# GAGAN_container_V1.net
KiCad netlist of a schematic drawn in EAGLE
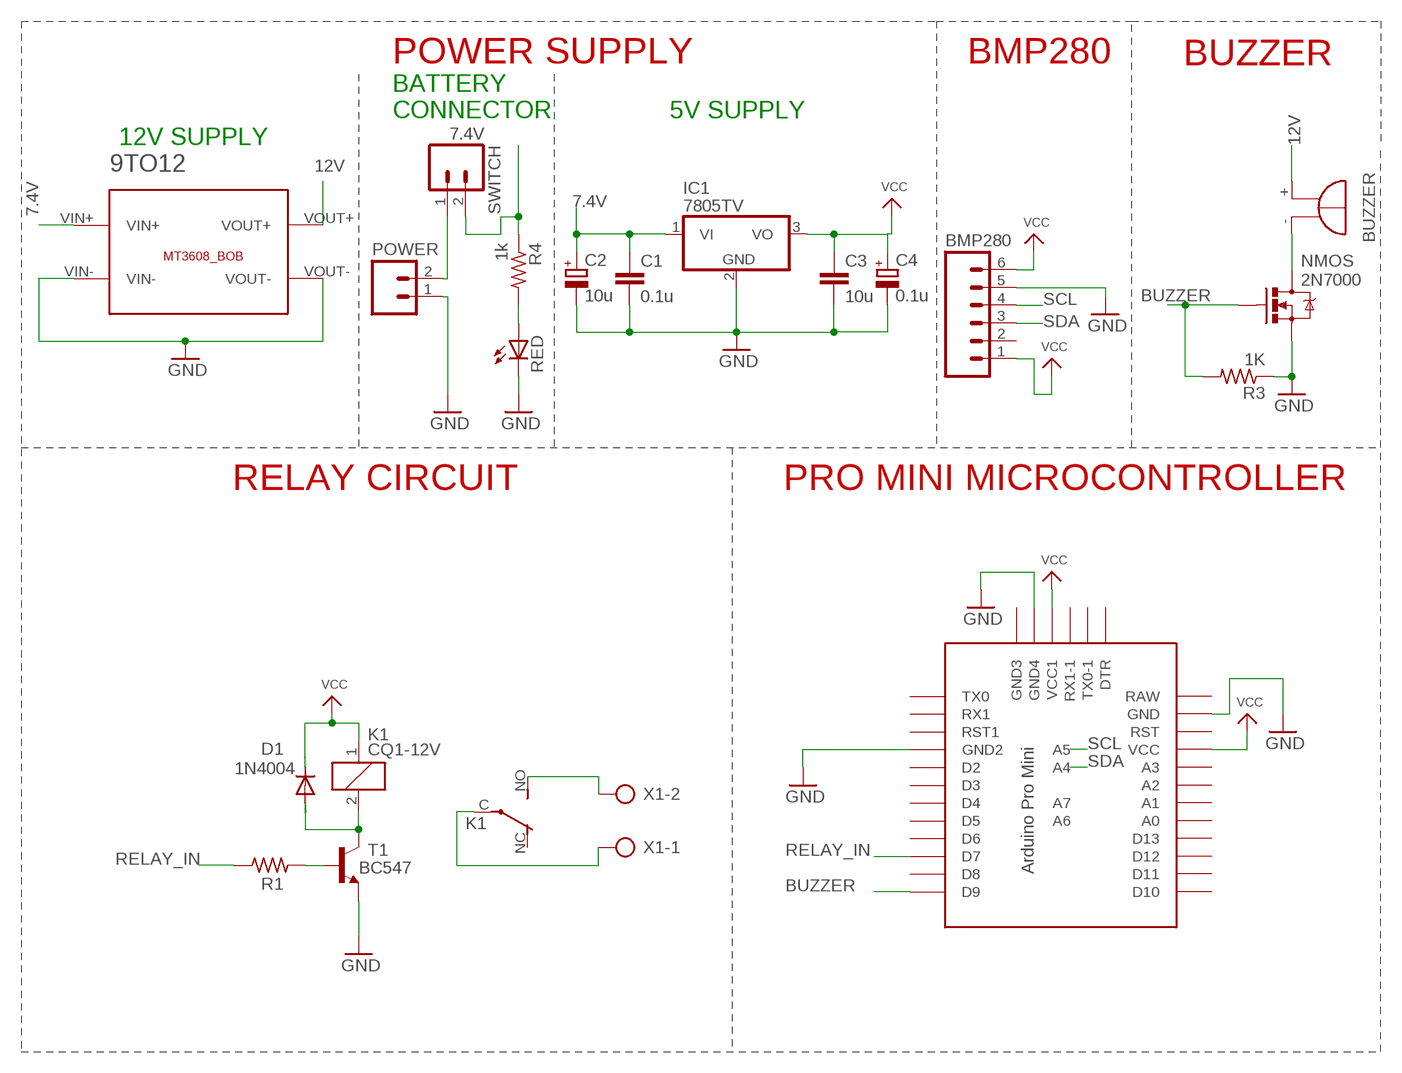
[diagram p0: schematic, sheet 1]

(export (version "E")
  (design (tool "Eeschema 10.0.6"))
  (components
    (comp (ref "9TO12")
      (value "BREAKOUTS_MT3608_BOB")
      (footprint "eagle-import:BREAKOUTS_MT3608_BOB")
      (libsource (lib "eagle-import") (part "BREAKOUTS_MT3608_BOB"))
    )
    (comp (ref "BMP280")
      (value "M06")
      (footprint "eagle-import:06P")
      (libsource (lib "eagle-import") (part "M06"))
    )
    (comp (ref "C1")
      (value "0.1u")
      (footprint "eagle-import:C025-025X050")
      (libsource (lib "eagle-import") (part "C-EU025-025X050"))
    )
    (comp (ref "C2")
      (value "10u")
      (footprint "eagle-import:E2,5-6")
      (libsource (lib "eagle-import") (part "CPOL-EUE2.5-6"))
    )
    (comp (ref "C3")
      (value "10u")
      (footprint "eagle-import:C025-025X050")
      (libsource (lib "eagle-import") (part "C-EU025-025X050"))
    )
    (comp (ref "C4")
      (value "0.1u")
      (footprint "eagle-import:E2,5-6")
      (libsource (lib "eagle-import") (part "CPOL-EUE2.5-6"))
    )
    (comp (ref "D1")
      (value "1N4004")
      (footprint "eagle-import:DO41-10")
      (libsource (lib "eagle-import") (part "1N4004"))
    )
    (comp (ref "IC1")
      (value "7805TV")
      (footprint "eagle-import:TO220V")
      (libsource (lib "eagle-import") (part "78TV05"))
    )
    (comp (ref "K1")
      (value "CQ1-12V")
      (footprint "eagle-import:CQ1")
      (libsource (lib "eagle-import") (part "CQ1-12V"))
    )
    (comp (ref "POWER")
      (value "CEDT_JANUARY_2015_V5_M02")
      (footprint "eagle-import:CEDT_JANUARY_2015_V5_02P")
      (libsource (lib "eagle-import") (part "CEDT_JANUARY_2015_V5_M02"))
    )
    (comp (ref "Q1")
      (value "SPARKFUN-DISCRETESEMI_MOSFET-NCHANNEL2N7000")
      (footprint "eagle-import:SPARKFUN-DISCRETESEMI_TO-92")
      (libsource (lib "eagle-import") (part "SPARKFUN-DISCRETESEMI_MOSFET-NCHANNEL2N7000"))
    )
    (comp (ref "R1")
      (value "R-US_0207/7")
      (footprint "eagle-import:0207_7")
      (libsource (lib "eagle-import") (part "R-US_0207/7"))
    )
    (comp (ref "R3")
      (value "1K")
      (footprint "eagle-import:0204_7")
      (libsource (lib "eagle-import") (part "R-US_0204/7"))
    )
    (comp (ref "R4")
      (value "1k")
      (footprint "eagle-import:0204_7")
      (libsource (lib "eagle-import") (part "R-US_0204/7"))
    )
    (comp (ref "RED")
      (value "red")
      (footprint "eagle-import:LED3MM")
      (libsource (lib "eagle-import") (part "LED3MM"))
    )
    (comp (ref "SG1")
      (value "BUZZER_EB2209A")
      (footprint "eagle-import:BUZZER_EB2209A")
      (libsource (lib "eagle-import") (part "BUZZER_EB2209A"))
    )
    (comp (ref "SWITCH")
      (value "M02")
      (footprint "eagle-import:02P")
      (libsource (lib "eagle-import") (part "M02"))
    )
    (comp (ref "T1")
      (value "BC547")
      (footprint "eagle-import:TO92")
      (libsource (lib "eagle-import") (part "BC547"))
    )
    (comp (ref "U$1")
      (value "PRO-MINI-2")
      (footprint "eagle-import:PRO-MINI-2")
      (libsource (lib "eagle-import") (part "PRO-MINI-2"))
    )
    (comp (ref "X1")
      (value "AK500/2-H")
      (footprint "eagle-import:AK500_2-H")
      (libsource (lib "eagle-import") (part "AK500/2-H"))
    )
  )
  (nets
    (net (code "1") (name "/7.4V") (class "Default")
      (node (ref "9TO12") (pin "VIN+") (pinfunction "VIN+_VIN+") (pintype "bidirectional"))
      (node (ref "C1") (pin "1") (pinfunction "1_1") (pintype "passive"))
      (node (ref "C2") (pin "+") (pinfunction "+_+") (pintype "passive"))
      (node (ref "IC1") (pin "1") (pinfunction "VI_1") (pintype "input"))
      (node (ref "R4") (pin "1") (pinfunction "1_1") (pintype "passive"))
      (node (ref "SWITCH") (pin "2") (pinfunction "2_2") (pintype "passive"))
    )
    (net (code "2") (name "/12V") (class "Default")
      (node (ref "9TO12") (pin "VOUT+") (pinfunction "VOUT+_VOUT+") (pintype "bidirectional"))
      (node (ref "SG1") (pin "+") (pinfunction "+_+") (pintype "passive"))
    )
    (net (code "3") (name "/BUZZER") (class "Default")
      (node (ref "Q1") (pin "2") (pinfunction "G_2") (pintype "passive"))
      (node (ref "R3") (pin "2") (pinfunction "2_2") (pintype "passive"))
      (node (ref "U$1") (pin "D9") (pinfunction "D9_D9") (pintype "bidirectional"))
    )
    (net (code "4") (name "/RELAY_IN") (class "Default")
      (node (ref "R1") (pin "1") (pinfunction "1_1") (pintype "passive"))
      (node (ref "U$1") (pin "D7") (pinfunction "D7_D7") (pintype "bidirectional"))
    )
    (net (code "5") (name "/SCL") (class "Default")
      (node (ref "BMP280") (pin "4") (pinfunction "4_4") (pintype "passive"))
      (node (ref "U$1") (pin "A5") (pinfunction "A5_A5") (pintype "bidirectional"))
    )
    (net (code "6") (name "/SDA") (class "Default")
      (node (ref "BMP280") (pin "3") (pinfunction "3_3") (pintype "passive"))
      (node (ref "U$1") (pin "A4") (pinfunction "A4_A4") (pintype "bidirectional"))
    )
    (net (code "7") (name "GND") (class "Default")
      (node (ref "9TO12") (pin "VIN-") (pinfunction "VIN-_VIN-") (pintype "bidirectional"))
      (node (ref "9TO12") (pin "VOUT-") (pinfunction "VOUT-_VOUT-") (pintype "bidirectional"))
      (node (ref "BMP280") (pin "5") (pinfunction "5_5") (pintype "passive"))
      (node (ref "C1") (pin "2") (pinfunction "2_2") (pintype "passive"))
      (node (ref "C2") (pin "-") (pinfunction "-_-") (pintype "passive"))
      (node (ref "C3") (pin "2") (pinfunction "2_2") (pintype "passive"))
      (node (ref "C4") (pin "-") (pinfunction "-_-") (pintype "passive"))
      (node (ref "IC1") (pin "2") (pinfunction "GND_2") (pintype "passive"))
      (node (ref "POWER") (pin "1") (pinfunction "1_1") (pintype "passive"))
      (node (ref "Q1") (pin "1") (pinfunction "S_1") (pintype "passive"))
      (node (ref "R3") (pin "1") (pinfunction "1_1") (pintype "passive"))
      (node (ref "RED") (pin "K") (pinfunction "C_K") (pintype "passive"))
      (node (ref "T1") (pin "1") (pinfunction "E_1") (pintype "passive"))
      (node (ref "U$1") (pin "GND") (pinfunction "GND_GND") (pintype "bidirectional"))
      (node (ref "U$1") (pin "GND1") (pinfunction "GND2_GND1") (pintype "bidirectional"))
      (node (ref "U$1") (pin "GND3") (pinfunction "GND4_GND3") (pintype "bidirectional"))
    )
    (net (code "8") (name "Net-(K1B-P)") (class "Default")
      (node (ref "K1") (pin "C") (pinfunction "P_C") (pintype "passive"))
      (node (ref "X1") (pin "1") (pinfunction "KL_1") (pintype "passive"))
    )
    (net (code "9") (name "Net-(K1B-S)") (class "Default")
      (node (ref "K1") (pin "NO") (pinfunction "S_NO") (pintype "passive"))
      (node (ref "X1") (pin "2") (pinfunction "KL_2") (pintype "passive"))
    )
    (net (code "10") (name "Net-(POWER-Pad2)") (class "Default")
      (node (ref "POWER") (pin "2") (pinfunction "2_2") (pintype "passive"))
      (node (ref "SWITCH") (pin "1") (pinfunction "1_1") (pintype "passive"))
    )
    (net (code "11") (name "Net-(Q1-D)") (class "Default")
      (node (ref "Q1") (pin "3") (pinfunction "D_3") (pintype "passive"))
      (node (ref "SG1") (pin "-") (pinfunction "-_-") (pintype "passive"))
    )
    (net (code "12") (name "Net-(R4-Pad2)") (class "Default")
      (node (ref "R4") (pin "2") (pinfunction "2_2") (pintype "passive"))
      (node (ref "RED") (pin "A") (pinfunction "A_A") (pintype "passive"))
    )
    (net (code "13") (name "Net-(T1-B)") (class "Default")
      (node (ref "R1") (pin "2") (pinfunction "2_2") (pintype "passive"))
      (node (ref "T1") (pin "2") (pinfunction "B_2") (pintype "passive"))
    )
    (net (code "14") (name "Net-(T1-C)") (class "Default")
      (node (ref "D1") (pin "A") (pinfunction "A_A") (pintype "passive"))
      (node (ref "K1") (pin "2") (pinfunction "2_2") (pintype "passive"))
      (node (ref "T1") (pin "3") (pinfunction "C_3") (pintype "passive"))
    )
    (net (code "15") (name "VCC") (class "Default")
      (node (ref "BMP280") (pin "1") (pinfunction "1_1") (pintype "passive"))
      (node (ref "BMP280") (pin "6") (pinfunction "6_6") (pintype "passive"))
      (node (ref "C3") (pin "1") (pinfunction "1_1") (pintype "passive"))
      (node (ref "C4") (pin "+") (pinfunction "+_+") (pintype "passive"))
      (node (ref "D1") (pin "C") (pinfunction "C_C") (pintype "passive"))
      (node (ref "IC1") (pin "3") (pinfunction "VO_3") (pintype "passive"))
      (node (ref "K1") (pin "1") (pinfunction "1_1") (pintype "passive"))
      (node (ref "U$1") (pin "VCC") (pinfunction "VCC_VCC") (pintype "bidirectional"))
      (node (ref "U$1") (pin "VCC1") (pinfunction "VCC1_VCC1") (pintype "bidirectional"))
    )
    (net (code "16") (name "unconnected-(BMP280-Pad2)") (class "Default")
      (node (ref "BMP280") (pin "2") (pinfunction "2_2") (pintype "passive"))
    )
    (net (code "17") (name "unconnected-(K1B-O-PadNC)") (class "Default")
      (node (ref "K1") (pin "NC") (pinfunction "O_NC") (pintype "passive"))
    )
    (net (code "18") (name "unconnected-(U$1-GND3-PadGND2)") (class "Default")
      (node (ref "U$1") (pin "GND2") (pinfunction "GND3_GND2") (pintype "bidirectional"))
    )
    (net (code "19") (name "unconnected-(U$1-PadA0)") (class "Default")
      (node (ref "U$1") (pin "A0") (pinfunction "A0_A0") (pintype "bidirectional"))
    )
    (net (code "20") (name "unconnected-(U$1-PadA1)") (class "Default")
      (node (ref "U$1") (pin "A1") (pinfunction "A1_A1") (pintype "bidirectional"))
    )
    (net (code "21") (name "unconnected-(U$1-PadA2)") (class "Default")
      (node (ref "U$1") (pin "A2") (pinfunction "A2_A2") (pintype "bidirectional"))
    )
    (net (code "22") (name "unconnected-(U$1-PadA3)") (class "Default")
      (node (ref "U$1") (pin "A3") (pinfunction "A3_A3") (pintype "bidirectional"))
    )
    (net (code "23") (name "unconnected-(U$1-PadA6)") (class "Default")
      (node (ref "U$1") (pin "A6") (pinfunction "A6_A6") (pintype "bidirectional"))
    )
    (net (code "24") (name "unconnected-(U$1-PadA7)") (class "Default")
      (node (ref "U$1") (pin "A7") (pinfunction "A7_A7") (pintype "bidirectional"))
    )
    (net (code "25") (name "unconnected-(U$1-PadD2)") (class "Default")
      (node (ref "U$1") (pin "D2") (pinfunction "D2_D2") (pintype "bidirectional"))
    )
    (net (code "26") (name "unconnected-(U$1-PadD3)") (class "Default")
      (node (ref "U$1") (pin "D3") (pinfunction "D3_D3") (pintype "bidirectional"))
    )
    (net (code "27") (name "unconnected-(U$1-PadD4)") (class "Default")
      (node (ref "U$1") (pin "D4") (pinfunction "D4_D4") (pintype "bidirectional"))
    )
    (net (code "28") (name "unconnected-(U$1-PadD5)") (class "Default")
      (node (ref "U$1") (pin "D5") (pinfunction "D5_D5") (pintype "bidirectional"))
    )
    (net (code "29") (name "unconnected-(U$1-PadD6)") (class "Default")
      (node (ref "U$1") (pin "D6") (pinfunction "D6_D6") (pintype "bidirectional"))
    )
    (net (code "30") (name "unconnected-(U$1-PadD8)") (class "Default")
      (node (ref "U$1") (pin "D8") (pinfunction "D8_D8") (pintype "bidirectional"))
    )
    (net (code "31") (name "unconnected-(U$1-PadD10)") (class "Default")
      (node (ref "U$1") (pin "D10") (pinfunction "D10_D10") (pintype "bidirectional"))
    )
    (net (code "32") (name "unconnected-(U$1-PadD11)") (class "Default")
      (node (ref "U$1") (pin "D11") (pinfunction "D11_D11") (pintype "bidirectional"))
    )
    (net (code "33") (name "unconnected-(U$1-PadD12)") (class "Default")
      (node (ref "U$1") (pin "D12") (pinfunction "D12_D12") (pintype "bidirectional"))
    )
    (net (code "34") (name "unconnected-(U$1-PadD13)") (class "Default")
      (node (ref "U$1") (pin "D13") (pinfunction "D13_D13") (pintype "bidirectional"))
    )
    (net (code "35") (name "unconnected-(U$1-PadDTR)") (class "Default")
      (node (ref "U$1") (pin "DTR") (pinfunction "DTR_DTR") (pintype "bidirectional"))
    )
    (net (code "36") (name "unconnected-(U$1-PadRAW)") (class "Default")
      (node (ref "U$1") (pin "RAW") (pinfunction "RAW_RAW") (pintype "bidirectional"))
    )
    (net (code "37") (name "unconnected-(U$1-PadRST)") (class "Default")
      (node (ref "U$1") (pin "RST") (pinfunction "RST_RST") (pintype "bidirectional"))
    )
    (net (code "38") (name "unconnected-(U$1-PadRST1)") (class "Default")
      (node (ref "U$1") (pin "RST1") (pinfunction "RST1_RST1") (pintype "bidirectional"))
    )
    (net (code "39") (name "unconnected-(U$1-PadRX1)") (class "Default")
      (node (ref "U$1") (pin "RX1") (pinfunction "RX1_RX1") (pintype "bidirectional"))
    )
    (net (code "40") (name "unconnected-(U$1-PadRX1-1)") (class "Default")
      (node (ref "U$1") (pin "RX1-1") (pinfunction "RX1-1_RX1-1") (pintype "bidirectional"))
    )
    (net (code "41") (name "unconnected-(U$1-PadTX0)") (class "Default")
      (node (ref "U$1") (pin "TX0") (pinfunction "TX0_TX0") (pintype "bidirectional"))
    )
    (net (code "42") (name "unconnected-(U$1-PadTX0-1)") (class "Default")
      (node (ref "U$1") (pin "TX0-1") (pinfunction "TX0-1_TX0-1") (pintype "bidirectional"))
    )
  )
)
